# Week2ATTINY4-5-9-10.net
KiCad netlist of a schematic drawn in EAGLE
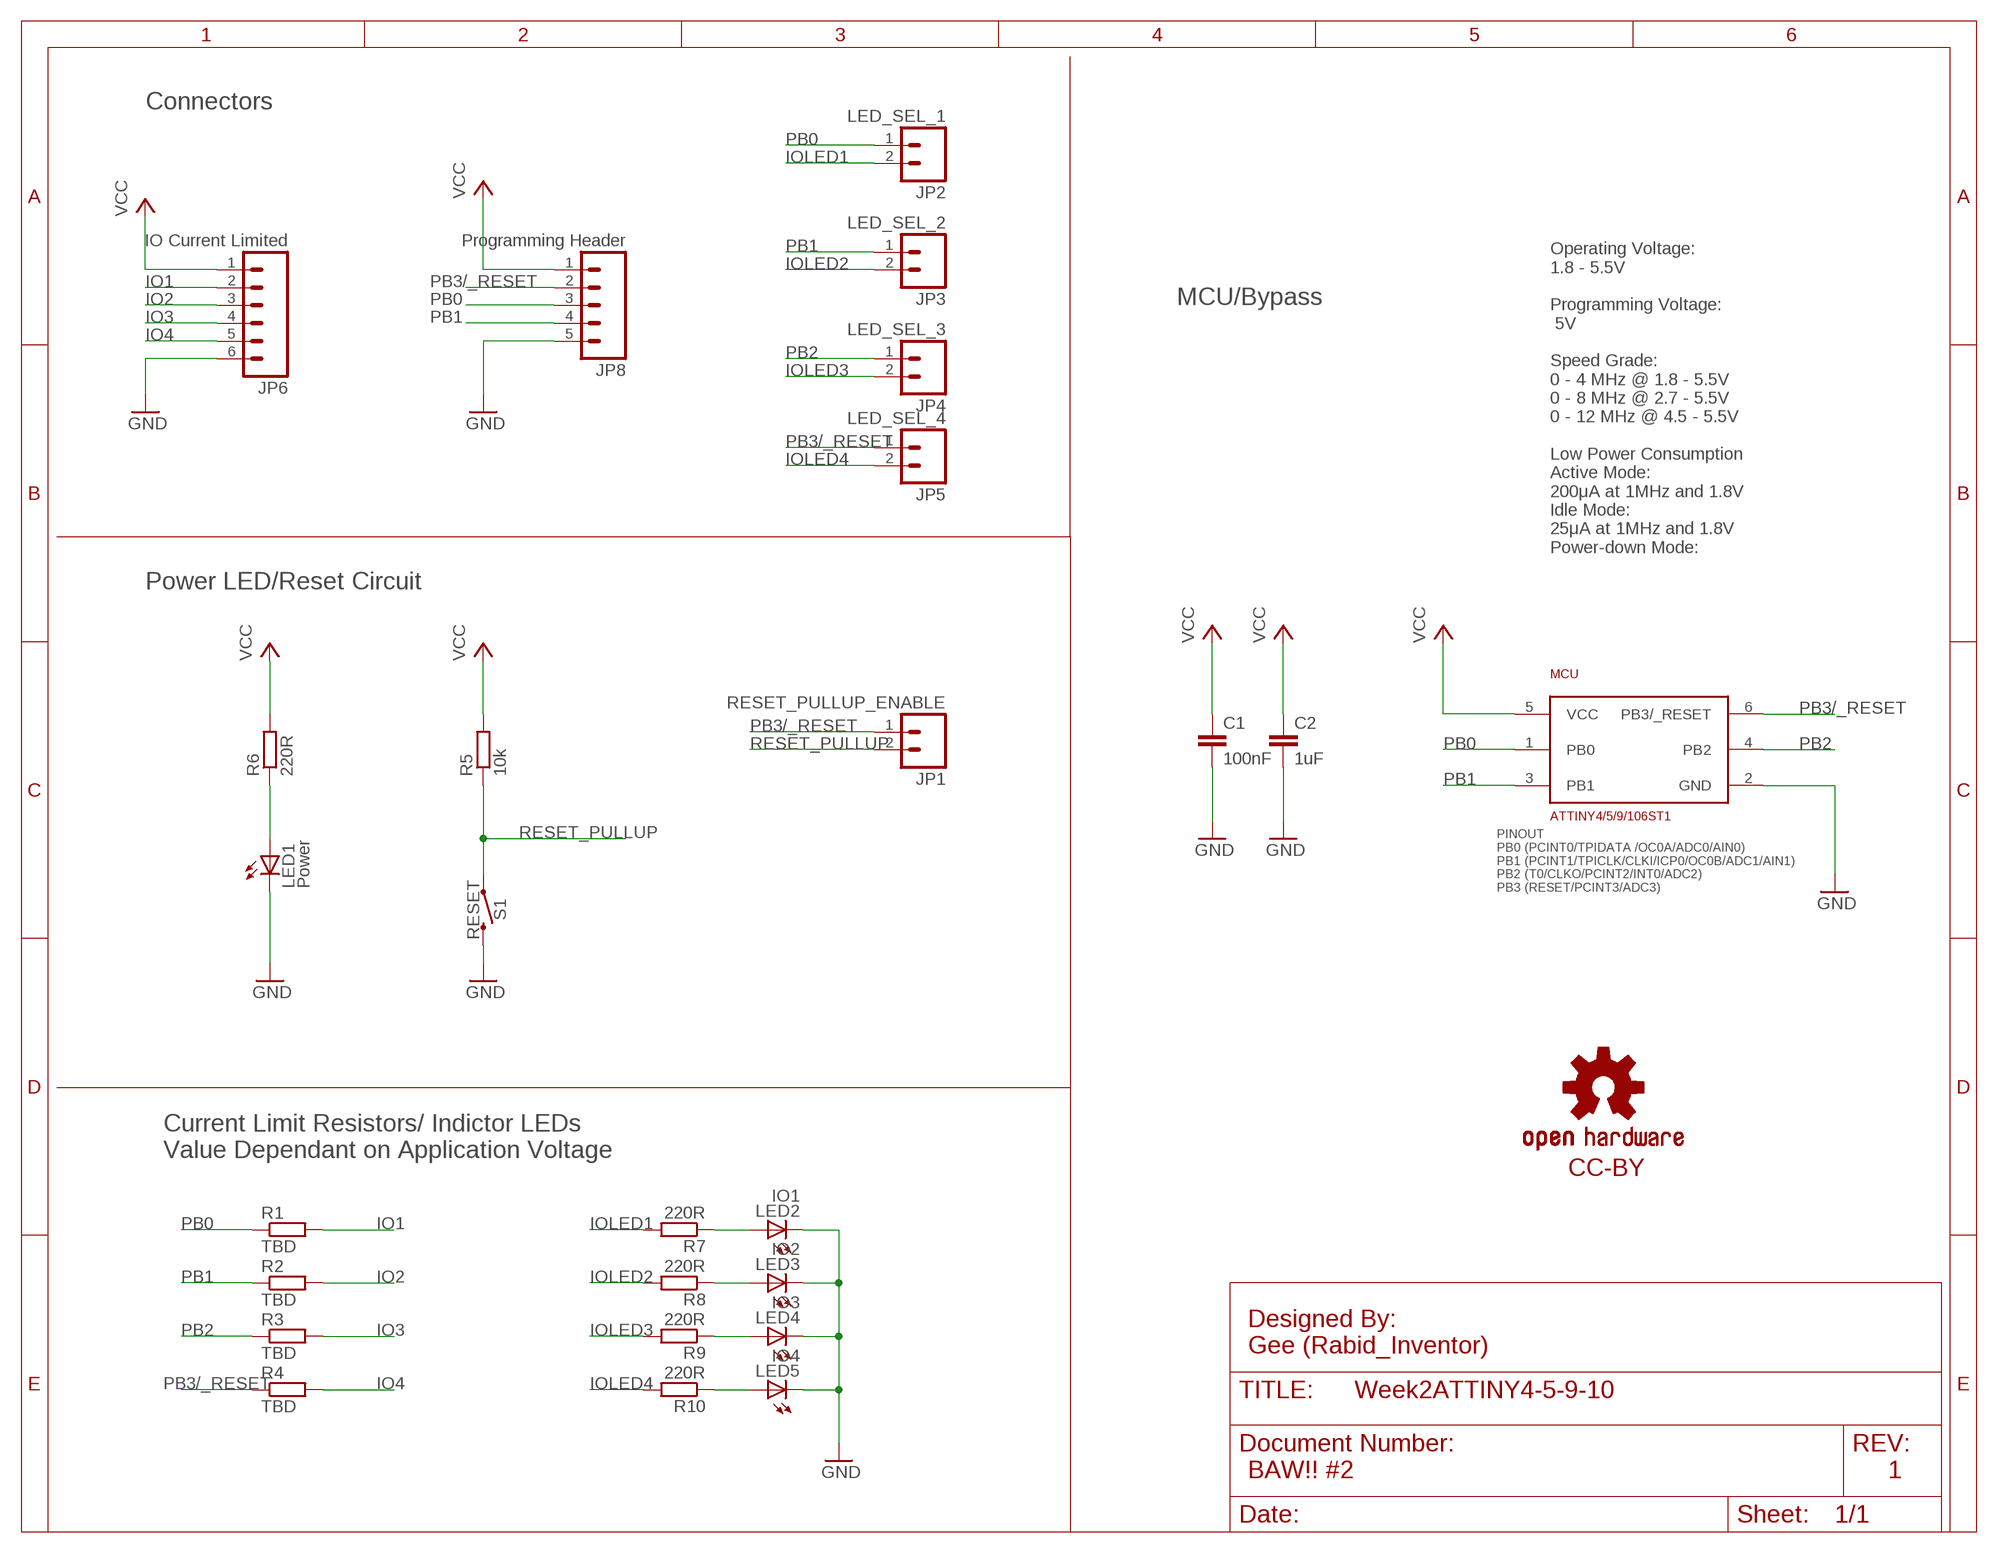
[diagram p0: schematic, sheet 1]

(export (version "E")
  (design (tool "Eeschema 10.0.6"))
  (components
    (comp (ref "C1")
      (value "100nF")
      (footprint "eagle-import:C0603K")
      (libsource (lib "eagle-import") (part "C-EUC0603K"))
    )
    (comp (ref "C2")
      (value "1uF")
      (footprint "eagle-import:C0603K")
      (libsource (lib "eagle-import") (part "C-EUC0603K"))
    )
    (comp (ref "JP1")
      (value "RESET_PULLUP_ENABLE")
      (footprint "eagle-import:1X02_NO_SILK")
      (libsource (lib "eagle-import") (part "M021X02_NO_SILK"))
    )
    (comp (ref "JP2")
      (value "LED_SEL_1")
      (footprint "eagle-import:1X02_NO_SILK")
      (libsource (lib "eagle-import") (part "M021X02_NO_SILK"))
    )
    (comp (ref "JP3")
      (value "LED_SEL_2")
      (footprint "eagle-import:1X02_NO_SILK")
      (libsource (lib "eagle-import") (part "M021X02_NO_SILK"))
    )
    (comp (ref "JP4")
      (value "LED_SEL_3")
      (footprint "eagle-import:1X02_NO_SILK")
      (libsource (lib "eagle-import") (part "M021X02_NO_SILK"))
    )
    (comp (ref "JP5")
      (value "LED_SEL_4")
      (footprint "eagle-import:1X02_NO_SILK")
      (libsource (lib "eagle-import") (part "M021X02_NO_SILK"))
    )
    (comp (ref "JP6")
      (value "IO Current Limited")
      (footprint "eagle-import:1X06_NO_SILK")
      (libsource (lib "eagle-import") (part "M06NO_SILK"))
    )
    (comp (ref "JP8")
      (value "Programming Header")
      (footprint "eagle-import:1X05_NO_SILK")
      (libsource (lib "eagle-import") (part "M05NO_SILK"))
    )
    (comp (ref "LED1")
      (value "Power")
      (footprint "eagle-import:CHIPLED_0805")
      (libsource (lib "eagle-import") (part "LEDCHIPLED_0805"))
    )
    (comp (ref "LED2")
      (value "IO1")
      (footprint "eagle-import:CHIPLED_0805")
      (libsource (lib "eagle-import") (part "LEDCHIPLED_0805"))
    )
    (comp (ref "LED3")
      (value "IO2")
      (footprint "eagle-import:CHIPLED_0805")
      (libsource (lib "eagle-import") (part "LEDCHIPLED_0805"))
    )
    (comp (ref "LED4")
      (value "IO3")
      (footprint "eagle-import:CHIPLED_0805")
      (libsource (lib "eagle-import") (part "LEDCHIPLED_0805"))
    )
    (comp (ref "LED5")
      (value "IO4")
      (footprint "eagle-import:CHIPLED_0805")
      (libsource (lib "eagle-import") (part "LEDCHIPLED_0805"))
    )
    (comp (ref "LOGO1")
      (value "OSHW-LOGOMINI")
      (footprint "eagle-import:OSHW-LOGO-MINI")
      (libsource (lib "eagle-import") (part "OSHW-LOGOMINI"))
    )
    (comp (ref "MCU")
      (value "ATTINY4/5/9/106ST1")
      (footprint "eagle-import:SOT23-6AVR")
      (libsource (lib "eagle-import") (part "ATTINY4/5/9/106ST1"))
    )
    (comp (ref "R1")
      (value "TBD")
      (footprint "eagle-import:R0603")
      (libsource (lib "eagle-import") (part "R-EU_R0603"))
    )
    (comp (ref "R2")
      (value "TBD")
      (footprint "eagle-import:R0603")
      (libsource (lib "eagle-import") (part "R-EU_R0603"))
    )
    (comp (ref "R3")
      (value "TBD")
      (footprint "eagle-import:R0603")
      (libsource (lib "eagle-import") (part "R-EU_R0603"))
    )
    (comp (ref "R4")
      (value "TBD")
      (footprint "eagle-import:R0603")
      (libsource (lib "eagle-import") (part "R-EU_R0603"))
    )
    (comp (ref "R5")
      (value "10k")
      (footprint "eagle-import:R0603")
      (libsource (lib "eagle-import") (part "R-EU_R0603"))
    )
    (comp (ref "R6")
      (value "220R")
      (footprint "eagle-import:R0603")
      (libsource (lib "eagle-import") (part "R-EU_R0603"))
    )
    (comp (ref "R7")
      (value "220R")
      (footprint "eagle-import:R0603")
      (libsource (lib "eagle-import") (part "R-EU_R0603"))
    )
    (comp (ref "R8")
      (value "220R")
      (footprint "eagle-import:R0603")
      (libsource (lib "eagle-import") (part "R-EU_R0603"))
    )
    (comp (ref "R9")
      (value "220R")
      (footprint "eagle-import:R0603")
      (libsource (lib "eagle-import") (part "R-EU_R0603"))
    )
    (comp (ref "R10")
      (value "220R")
      (footprint "eagle-import:R0603")
      (libsource (lib "eagle-import") (part "R-EU_R0603"))
    )
    (comp (ref "S1")
      (value "RESET")
      (footprint "eagle-import:TACTILE_SWITCH_PTH_6.0MM")
      (libsource (lib "eagle-import") (part "MOMENTARY-SWITCH-SPST-PTH-6.0MM"))
    )
  )
  (nets
    (net (code "1") (name "/IO1") (class "Default")
      (node (ref "JP6") (pin "2") (pinfunction "2_2") (pintype "passive"))
      (node (ref "R1") (pin "2") (pinfunction "2_2") (pintype "passive"))
    )
    (net (code "2") (name "/IO2") (class "Default")
      (node (ref "JP6") (pin "3") (pinfunction "3_3") (pintype "passive"))
      (node (ref "R2") (pin "2") (pinfunction "2_2") (pintype "passive"))
    )
    (net (code "3") (name "/IO3") (class "Default")
      (node (ref "JP6") (pin "4") (pinfunction "4_4") (pintype "passive"))
      (node (ref "R3") (pin "2") (pinfunction "2_2") (pintype "passive"))
    )
    (net (code "4") (name "/IO4") (class "Default")
      (node (ref "JP6") (pin "5") (pinfunction "5_5") (pintype "passive"))
      (node (ref "R4") (pin "2") (pinfunction "2_2") (pintype "passive"))
    )
    (net (code "5") (name "/IOLED1") (class "Default")
      (node (ref "JP2") (pin "2") (pinfunction "2_2") (pintype "passive"))
      (node (ref "R7") (pin "2") (pinfunction "2_2") (pintype "passive"))
    )
    (net (code "6") (name "/IOLED2") (class "Default")
      (node (ref "JP3") (pin "2") (pinfunction "2_2") (pintype "passive"))
      (node (ref "R8") (pin "2") (pinfunction "2_2") (pintype "passive"))
    )
    (net (code "7") (name "/IOLED3") (class "Default")
      (node (ref "JP4") (pin "2") (pinfunction "2_2") (pintype "passive"))
      (node (ref "R9") (pin "2") (pinfunction "2_2") (pintype "passive"))
    )
    (net (code "8") (name "/IOLED4") (class "Default")
      (node (ref "JP5") (pin "2") (pinfunction "2_2") (pintype "passive"))
      (node (ref "R10") (pin "2") (pinfunction "2_2") (pintype "passive"))
    )
    (net (code "9") (name "/PB0") (class "Default")
      (node (ref "JP2") (pin "1") (pinfunction "1_1") (pintype "passive"))
      (node (ref "JP8") (pin "3") (pinfunction "3_3") (pintype "passive"))
      (node (ref "MCU") (pin "1") (pinfunction "PB0_1") (pintype "bidirectional"))
      (node (ref "R1") (pin "1") (pinfunction "1_1") (pintype "passive"))
    )
    (net (code "10") (name "/PB1") (class "Default")
      (node (ref "JP3") (pin "1") (pinfunction "1_1") (pintype "passive"))
      (node (ref "JP8") (pin "4") (pinfunction "4_4") (pintype "passive"))
      (node (ref "MCU") (pin "3") (pinfunction "PB1_3") (pintype "bidirectional"))
      (node (ref "R2") (pin "1") (pinfunction "1_1") (pintype "passive"))
    )
    (net (code "11") (name "/PB2") (class "Default")
      (node (ref "JP4") (pin "1") (pinfunction "1_1") (pintype "passive"))
      (node (ref "MCU") (pin "4") (pinfunction "PB2_4") (pintype "bidirectional"))
      (node (ref "R3") (pin "1") (pinfunction "1_1") (pintype "passive"))
    )
    (net (code "12") (name "/PB3{slash}_RESET") (class "Default")
      (node (ref "JP1") (pin "1") (pinfunction "1_1") (pintype "passive"))
      (node (ref "JP5") (pin "1") (pinfunction "1_1") (pintype "passive"))
      (node (ref "JP8") (pin "2") (pinfunction "2_2") (pintype "passive"))
      (node (ref "MCU") (pin "6") (pinfunction "PB3/_RESET_6") (pintype "bidirectional"))
      (node (ref "R4") (pin "1") (pinfunction "1_1") (pintype "passive"))
    )
    (net (code "13") (name "/RESET_PULLUP") (class "Default")
      (node (ref "JP1") (pin "2") (pinfunction "2_2") (pintype "passive"))
      (node (ref "R5") (pin "1") (pinfunction "1_1") (pintype "passive"))
      (node (ref "S1") (pin "1") (pinfunction "1_1") (pintype "passive"))
    )
    (net (code "14") (name "GND") (class "Default")
      (node (ref "C1") (pin "2") (pinfunction "2_2") (pintype "passive"))
      (node (ref "C2") (pin "2") (pinfunction "2_2") (pintype "passive"))
      (node (ref "JP6") (pin "6") (pinfunction "6_6") (pintype "passive"))
      (node (ref "JP8") (pin "5") (pinfunction "5_5") (pintype "passive"))
      (node (ref "LED1") (pin "C") (pinfunction "C_C") (pintype "passive"))
      (node (ref "LED2") (pin "C") (pinfunction "C_C") (pintype "passive"))
      (node (ref "LED3") (pin "C") (pinfunction "C_C") (pintype "passive"))
      (node (ref "LED4") (pin "C") (pinfunction "C_C") (pintype "passive"))
      (node (ref "LED5") (pin "C") (pinfunction "C_C") (pintype "passive"))
      (node (ref "MCU") (pin "2") (pinfunction "GND_2") (pintype "power_in"))
      (node (ref "S1") (pin "3") (pinfunction "2_3") (pintype "passive"))
    )
    (net (code "15") (name "Net-(LED1-PadA)") (class "Default")
      (node (ref "LED1") (pin "A") (pinfunction "A_A") (pintype "passive"))
      (node (ref "R6") (pin "1") (pinfunction "1_1") (pintype "passive"))
    )
    (net (code "16") (name "Net-(LED2-PadA)") (class "Default")
      (node (ref "LED2") (pin "A") (pinfunction "A_A") (pintype "passive"))
      (node (ref "R7") (pin "1") (pinfunction "1_1") (pintype "passive"))
    )
    (net (code "17") (name "Net-(LED3-PadA)") (class "Default")
      (node (ref "LED3") (pin "A") (pinfunction "A_A") (pintype "passive"))
      (node (ref "R8") (pin "1") (pinfunction "1_1") (pintype "passive"))
    )
    (net (code "18") (name "Net-(LED4-PadA)") (class "Default")
      (node (ref "LED4") (pin "A") (pinfunction "A_A") (pintype "passive"))
      (node (ref "R9") (pin "1") (pinfunction "1_1") (pintype "passive"))
    )
    (net (code "19") (name "Net-(LED5-PadA)") (class "Default")
      (node (ref "LED5") (pin "A") (pinfunction "A_A") (pintype "passive"))
      (node (ref "R10") (pin "1") (pinfunction "1_1") (pintype "passive"))
    )
    (net (code "20") (name "VCC") (class "Default")
      (node (ref "C1") (pin "1") (pinfunction "1_1") (pintype "passive"))
      (node (ref "C2") (pin "1") (pinfunction "1_1") (pintype "passive"))
      (node (ref "JP6") (pin "1") (pinfunction "1_1") (pintype "passive"))
      (node (ref "JP8") (pin "1") (pinfunction "1_1") (pintype "passive"))
      (node (ref "MCU") (pin "5") (pinfunction "VCC_5") (pintype "power_in"))
      (node (ref "R5") (pin "2") (pinfunction "2_2") (pintype "passive"))
      (node (ref "R6") (pin "2") (pinfunction "2_2") (pintype "passive"))
    )
  )
)
